# PiHome_RFM69-95_to_nRF.net
KiCad netlist of a schematic drawn in EAGLE
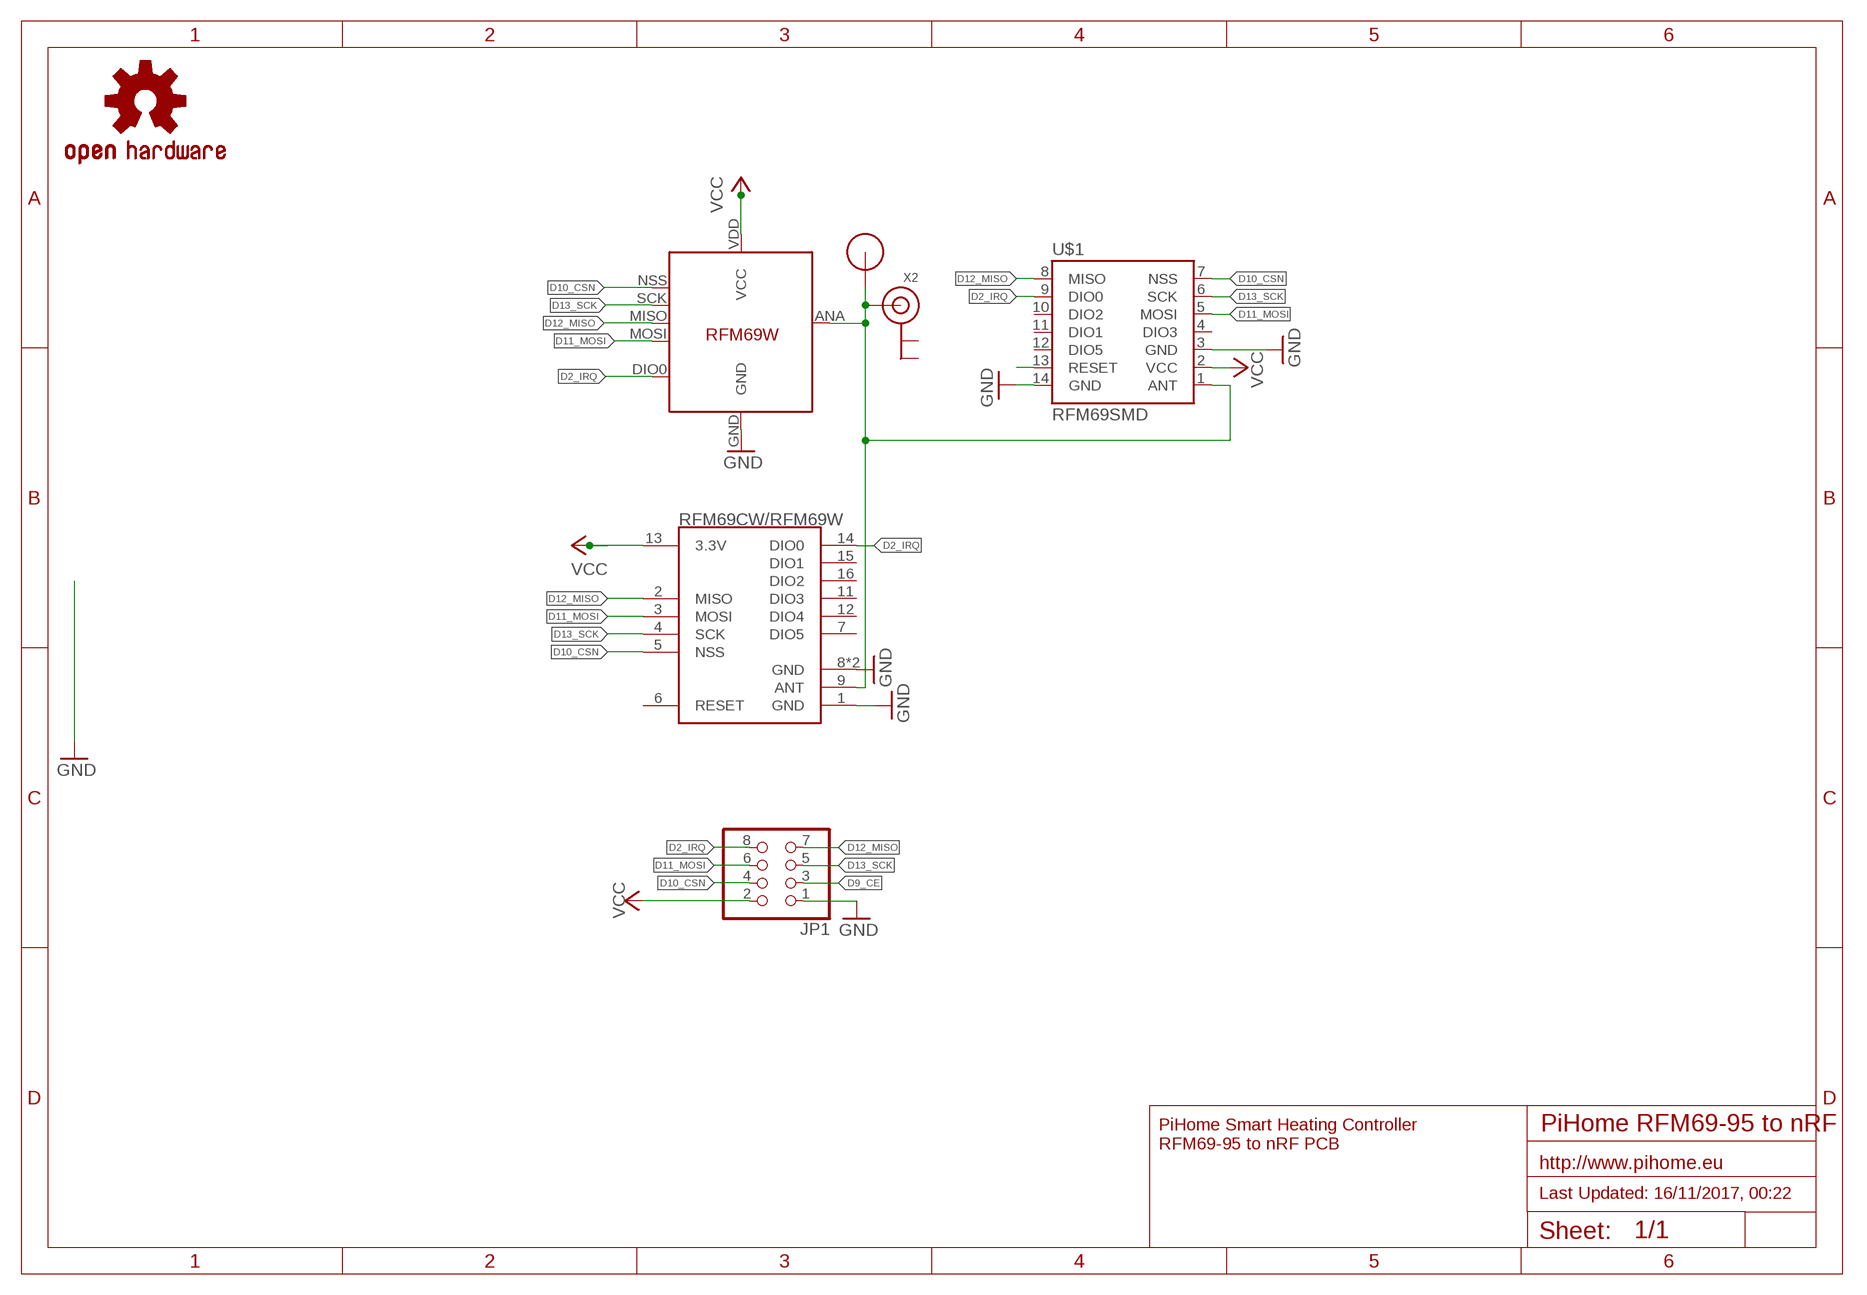
[diagram p0: schematic, sheet 1]

(export (version "E")
  (design (tool "Eeschema 10.0.6"))
  (components
    (comp (ref "JP1")
      (value "PINHD-2X4")
      (footprint "eagle-import:2X04")
      (libsource (lib "eagle-import") (part "PINHD-2X4"))
    )
    (comp (ref "LOGO2")
      (value "OSHW-LOGOS")
      (footprint "eagle-import:OSHW-LOGO-S")
      (libsource (lib "eagle-import") (part "OSHW-LOGOS"))
    )
    (comp (ref "RFM69CW/RFM69W")
      (value "RFM69HCW")
      (footprint "eagle-import:RFM69HCW-XXXS2")
      (libsource (lib "eagle-import") (part "RFM69HCW"))
    )
    (comp (ref "RFM69W-433MHZ")
      (value "RFM69")
      (footprint "eagle-import:RFM69W-MINPADS")
      (libsource (lib "eagle-import") (part "RFM69"))
    )
    (comp (ref "U$1")
      (value "RFM69SMD")
      (footprint "eagle-import:RFM69")
      (libsource (lib "eagle-import") (part "RFM69SMD"))
    )
    (comp (ref "U$6")
      (value "RFM12B_ANTENNA")
      (footprint "eagle-import:RFM12B-ANTENNA")
      (libsource (lib "eagle-import") (part "RFM12B_ANTENNA"))
    )
    (comp (ref "X2")
      (value "ANTENNA_U.FL")
      (footprint "eagle-import:U.FL")
      (libsource (lib "eagle-import") (part "ANTENNA_U.FL"))
    )
  )
  (nets
    (net (code "1") (name "D2_IRQ") (class "Default")
      (node (ref "JP1") (pin "8") (pinfunction "8_8") (pintype "passive"))
      (node (ref "RFM69CW/RFM69W") (pin "14") (pinfunction "DIO0_14") (pintype "bidirectional"))
      (node (ref "RFM69W-433MHZ") (pin "DIO0") (pinfunction "DIO0_DIO0") (pintype "open_collector"))
      (node (ref "U$1") (pin "9") (pinfunction "DIO0_9") (pintype "output"))
    )
    (net (code "2") (name "D9_CE") (class "Default")
      (node (ref "JP1") (pin "3") (pinfunction "3_3") (pintype "passive"))
    )
    (net (code "3") (name "D10_CSN") (class "Default")
      (node (ref "JP1") (pin "4") (pinfunction "4_4") (pintype "passive"))
      (node (ref "RFM69CW/RFM69W") (pin "5") (pinfunction "NSS_5") (pintype "input"))
      (node (ref "RFM69W-433MHZ") (pin "NSS") (pinfunction "SEL_NSS") (pintype "input"))
      (node (ref "U$1") (pin "7") (pinfunction "NSS_7") (pintype "output"))
    )
    (net (code "4") (name "D11_MOSI") (class "Default")
      (node (ref "JP1") (pin "6") (pinfunction "6_6") (pintype "passive"))
      (node (ref "RFM69CW/RFM69W") (pin "3") (pinfunction "MOSI_3") (pintype "input"))
      (node (ref "RFM69W-433MHZ") (pin "MOSI") (pinfunction "MOSI_MOSI") (pintype "output"))
      (node (ref "U$1") (pin "5") (pinfunction "MOSI_5") (pintype "input"))
    )
    (net (code "5") (name "D12_MISO") (class "Default")
      (node (ref "JP1") (pin "7") (pinfunction "7_7") (pintype "passive"))
      (node (ref "RFM69CW/RFM69W") (pin "2") (pinfunction "MISO_2") (pintype "bidirectional"))
      (node (ref "RFM69W-433MHZ") (pin "MISO") (pinfunction "MISO_MISO") (pintype "input"))
      (node (ref "U$1") (pin "8") (pinfunction "MISO_8") (pintype "input"))
    )
    (net (code "6") (name "D13_SCK") (class "Default")
      (node (ref "JP1") (pin "5") (pinfunction "5_5") (pintype "passive"))
      (node (ref "RFM69CW/RFM69W") (pin "4") (pinfunction "SCK_4") (pintype "input"))
      (node (ref "RFM69W-433MHZ") (pin "SCK") (pinfunction "SCK_SCK") (pintype "input"))
      (node (ref "U$1") (pin "6") (pinfunction "SCK_6") (pintype "input"))
    )
    (net (code "7") (name "GND") (class "Default")
      (node (ref "JP1") (pin "1") (pinfunction "1_1") (pintype "passive"))
      (node (ref "RFM69CW/RFM69W") (pin "1") (pinfunction "GND_1") (pintype "power_in"))
      (node (ref "RFM69CW/RFM69W") (pin "10") (pinfunction "GND_10") (pintype "power_in"))
      (node (ref "RFM69CW/RFM69W") (pin "8") (pinfunction "GND_8") (pintype "power_in"))
      (node (ref "RFM69W-433MHZ") (pin "GND") (pinfunction "GND_GND") (pintype "power_in"))
      (node (ref "U$1") (pin "14") (pinfunction "GND_14") (pintype "power_in"))
      (node (ref "U$1") (pin "3") (pinfunction "GND_3") (pintype "power_in"))
    )
    (net (code "8") (name "Net-(RFM69CW/RFM69W-ANT)") (class "Default")
      (node (ref "RFM69CW/RFM69W") (pin "9") (pinfunction "ANT_9") (pintype "passive"))
      (node (ref "RFM69W-433MHZ") (pin "ANA") (pinfunction "ANT_ANA") (pintype "passive"))
      (node (ref "U$1") (pin "1") (pinfunction "ANT_1") (pintype "bidirectional"))
      (node (ref "U$6") (pin "P$1") (pinfunction "1_P$1") (pintype "bidirectional"))
      (node (ref "X2") (pin "3") (pinfunction "SIGNAL_3") (pintype "passive"))
    )
    (net (code "9") (name "VCC") (class "Default")
      (node (ref "JP1") (pin "2") (pinfunction "2_2") (pintype "passive"))
      (node (ref "RFM69CW/RFM69W") (pin "13") (pinfunction "3.3V_13") (pintype "power_in"))
      (node (ref "RFM69W-433MHZ") (pin "VDD") (pinfunction "VCC_VDD") (pintype "power_in"))
      (node (ref "U$1") (pin "2") (pinfunction "VCC_2") (pintype "bidirectional"))
    )
    (net (code "10") (name "unconnected-(RFM69CW/RFM69W-DIO1-Pad15)") (class "Default")
      (node (ref "RFM69CW/RFM69W") (pin "15") (pinfunction "DIO1_15") (pintype "bidirectional"))
    )
    (net (code "11") (name "unconnected-(RFM69CW/RFM69W-DIO2-Pad16)") (class "Default")
      (node (ref "RFM69CW/RFM69W") (pin "16") (pinfunction "DIO2_16") (pintype "bidirectional"))
    )
    (net (code "12") (name "unconnected-(RFM69CW/RFM69W-DIO3-Pad11)") (class "Default")
      (node (ref "RFM69CW/RFM69W") (pin "11") (pinfunction "DIO3_11") (pintype "bidirectional"))
    )
    (net (code "13") (name "unconnected-(RFM69CW/RFM69W-DIO4-Pad12)") (class "Default")
      (node (ref "RFM69CW/RFM69W") (pin "12") (pinfunction "DIO4_12") (pintype "bidirectional"))
    )
    (net (code "14") (name "unconnected-(RFM69CW/RFM69W-DIO5-Pad7)") (class "Default")
      (node (ref "RFM69CW/RFM69W") (pin "7") (pinfunction "DIO5_7") (pintype "bidirectional"))
    )
    (net (code "15") (name "unconnected-(RFM69CW/RFM69W-RESET-Pad6)") (class "Default")
      (node (ref "RFM69CW/RFM69W") (pin "6") (pinfunction "RESET_6") (pintype "input"))
    )
    (net (code "16") (name "unconnected-(U$1-DIO1-Pad11)") (class "Default")
      (node (ref "U$1") (pin "11") (pinfunction "DIO1_11") (pintype "input"))
    )
    (net (code "17") (name "unconnected-(U$1-DIO2-Pad10)") (class "Default")
      (node (ref "U$1") (pin "10") (pinfunction "DIO2_10") (pintype "input"))
    )
    (net (code "18") (name "unconnected-(U$1-DIO3-Pad4)") (class "Default")
      (node (ref "U$1") (pin "4") (pinfunction "DIO3_4") (pintype "input"))
    )
    (net (code "19") (name "unconnected-(U$1-DIO5-Pad12)") (class "Default")
      (node (ref "U$1") (pin "12") (pinfunction "DIO5_12") (pintype "input"))
    )
    (net (code "20") (name "unconnected-(U$1-RESET-Pad13)") (class "Default")
      (node (ref "U$1") (pin "13") (pinfunction "RESET_13") (pintype "power_in"))
    )
    (net (code "21") (name "unconnected-(X2-GND-Pad1)") (class "Default")
      (node (ref "X2") (pin "1") (pinfunction "GND_1") (pintype "passive"))
    )
    (net (code "22") (name "unconnected-(X2-GND-Pad2)") (class "Default")
      (node (ref "X2") (pin "2") (pinfunction "GND_2") (pintype "passive"))
    )
  )
)
